# TestMod_SEAx_Base.net
KiCad netlist of a schematic drawn in Altium Designer
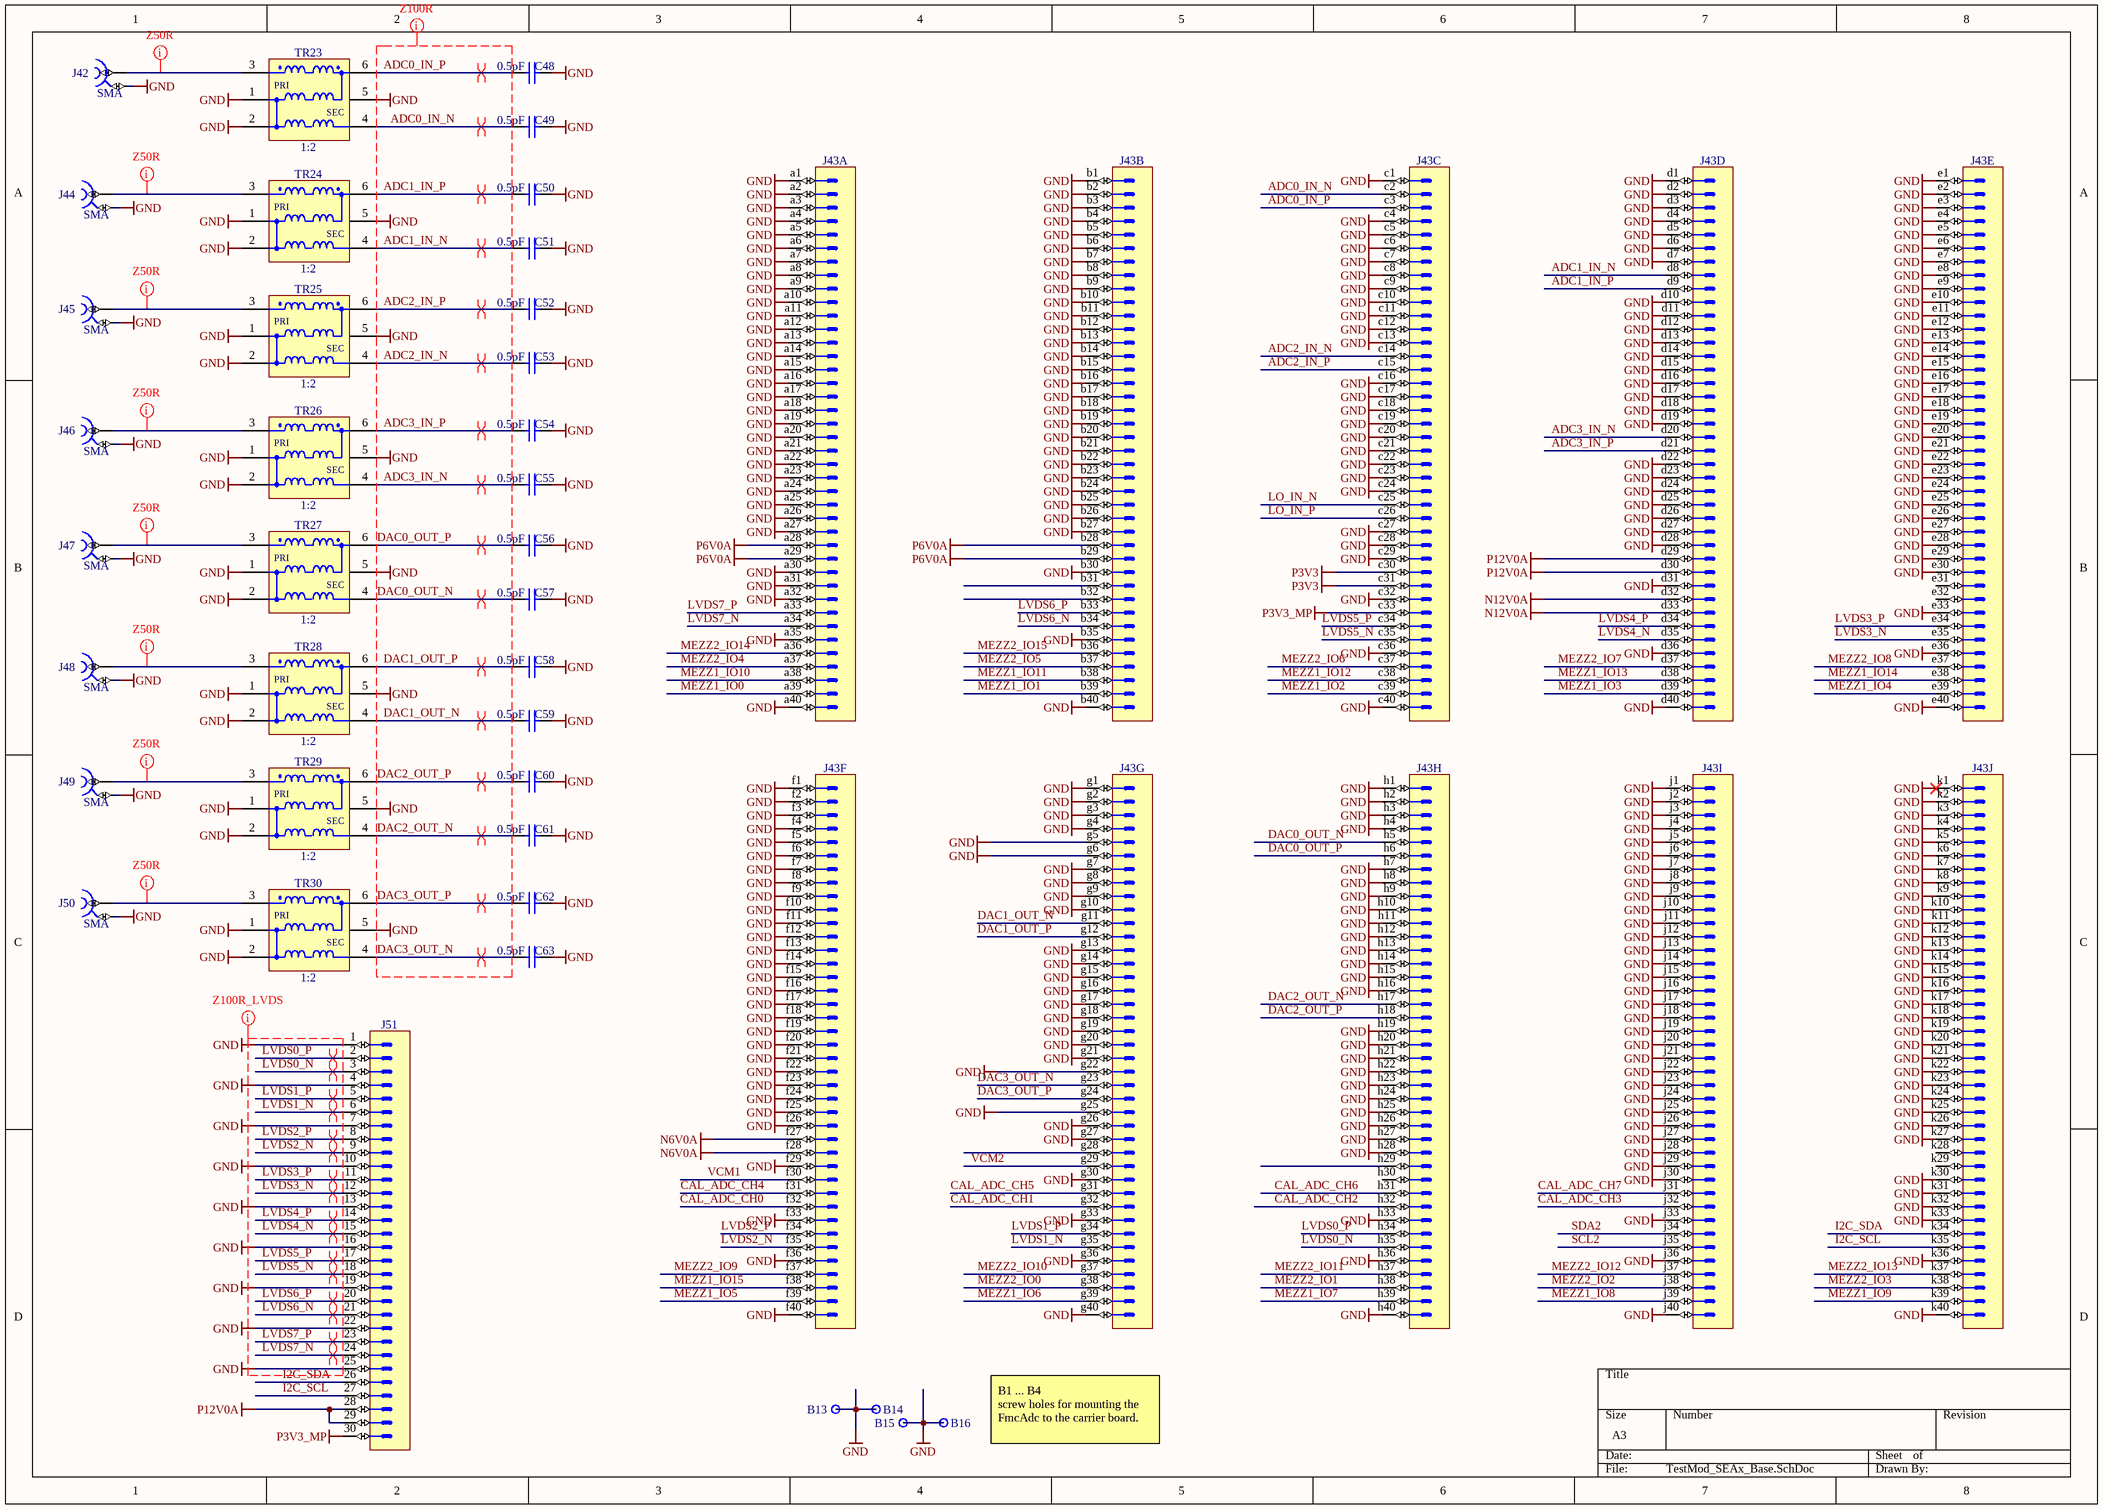
[diagram p0: TestMod_SEAx_Base.SchDoc]

(export (version "E")
  (design (tool "Eeschema 10.0.6"))
  (components
    (comp (ref "B13")
      (value "Plated Hole")
      (footprint "MTG270_500")
      (description "Single Terminal Socket")
      (fields (field (name "PART NUMBER") "PLATED_HOLE2.7_PAD5.0") (field (name "AUTHOR") "CERN DEM JMW"))
      (libsource (lib "Eletro-mechanical") (part "Single Terminal Socket"))
    )
    (comp (ref "B14")
      (value "Plated Hole")
      (footprint "MTG270_500")
      (description "Single Terminal Socket")
      (fields (field (name "PART NUMBER") "PLATED_HOLE2.7_PAD5.0") (field (name "AUTHOR") "CERN DEM JMW"))
      (libsource (lib "Eletro-mechanical") (part "Single Terminal Socket"))
    )
    (comp (ref "B15")
      (value "Plated Hole")
      (footprint "MTG270_500")
      (description "Single Terminal Socket")
      (fields (field (name "PART NUMBER") "PLATED_HOLE2.7_PAD5.0") (field (name "AUTHOR") "CERN DEM JMW"))
      (libsource (lib "Eletro-mechanical") (part "Single Terminal Socket"))
    )
    (comp (ref "B16")
      (value "Plated Hole")
      (footprint "MTG270_500")
      (description "Single Terminal Socket")
      (fields (field (name "PART NUMBER") "PLATED_HOLE2.7_PAD5.0") (field (name "AUTHOR") "CERN DEM JMW"))
      (libsource (lib "Eletro-mechanical") (part "Single Terminal Socket"))
    )
    (comp (ref "C48")
      (value "0.5pF")
      (footprint "CAPC1005X50N")
      (description "Non-polarised capacitor")
      (fields
        (field (name "PART NUMBER") "CC0402_0.5PF_25V_0.05PF_AVX_04023J0R5ABSTR")
        (field (name "VOLTAGE") "25V")
        (field (name "AUTHOR") "CERN DEM JLC")
      )
      (libsource (lib "Capacitors") (part "Capacitor - non polarized"))
    )
    (comp (ref "C49")
      (value "0.5pF")
      (footprint "CAPC1005X50N")
      (description "Non-polarised capacitor")
      (fields
        (field (name "PART NUMBER") "CC0402_0.5PF_25V_0.05PF_AVX_04023J0R5ABSTR")
        (field (name "VOLTAGE") "25V")
        (field (name "AUTHOR") "CERN DEM JLC")
      )
      (libsource (lib "Capacitors") (part "Capacitor - non polarized"))
    )
    (comp (ref "C50")
      (value "0.5pF")
      (footprint "CAPC1005X50N")
      (description "Non-polarised capacitor")
      (fields
        (field (name "PART NUMBER") "CC0402_0.5PF_25V_0.05PF_AVX_04023J0R5ABSTR")
        (field (name "VOLTAGE") "25V")
        (field (name "AUTHOR") "CERN DEM JLC")
      )
      (libsource (lib "Capacitors") (part "Capacitor - non polarized"))
    )
    (comp (ref "C51")
      (value "0.5pF")
      (footprint "CAPC1005X50N")
      (description "Non-polarised capacitor")
      (fields
        (field (name "PART NUMBER") "CC0402_0.5PF_25V_0.05PF_AVX_04023J0R5ABSTR")
        (field (name "VOLTAGE") "25V")
        (field (name "AUTHOR") "CERN DEM JLC")
      )
      (libsource (lib "Capacitors") (part "Capacitor - non polarized"))
    )
    (comp (ref "C52")
      (value "0.5pF")
      (footprint "CAPC1005X50N")
      (description "Non-polarised capacitor")
      (fields
        (field (name "PART NUMBER") "CC0402_0.5PF_25V_0.05PF_AVX_04023J0R5ABSTR")
        (field (name "VOLTAGE") "25V")
        (field (name "AUTHOR") "CERN DEM JLC")
      )
      (libsource (lib "Capacitors") (part "Capacitor - non polarized"))
    )
    (comp (ref "C53")
      (value "0.5pF")
      (footprint "CAPC1005X50N")
      (description "Non-polarised capacitor")
      (fields
        (field (name "PART NUMBER") "CC0402_0.5PF_25V_0.05PF_AVX_04023J0R5ABSTR")
        (field (name "VOLTAGE") "25V")
        (field (name "AUTHOR") "CERN DEM JLC")
      )
      (libsource (lib "Capacitors") (part "Capacitor - non polarized"))
    )
    (comp (ref "C54")
      (value "0.5pF")
      (footprint "CAPC1005X50N")
      (description "Non-polarised capacitor")
      (fields
        (field (name "PART NUMBER") "CC0402_0.5PF_25V_0.05PF_AVX_04023J0R5ABSTR")
        (field (name "VOLTAGE") "25V")
        (field (name "AUTHOR") "CERN DEM JLC")
      )
      (libsource (lib "Capacitors") (part "Capacitor - non polarized"))
    )
    (comp (ref "C55")
      (value "0.5pF")
      (footprint "CAPC1005X50N")
      (description "Non-polarised capacitor")
      (fields
        (field (name "PART NUMBER") "CC0402_0.5PF_25V_0.05PF_AVX_04023J0R5ABSTR")
        (field (name "VOLTAGE") "25V")
        (field (name "AUTHOR") "CERN DEM JLC")
      )
      (libsource (lib "Capacitors") (part "Capacitor - non polarized"))
    )
    (comp (ref "C56")
      (value "0.5pF")
      (footprint "CAPC1005X50N")
      (description "Non-polarised capacitor")
      (fields
        (field (name "PART NUMBER") "CC0402_0.5PF_25V_0.05PF_AVX_04023J0R5ABSTR")
        (field (name "VOLTAGE") "25V")
        (field (name "AUTHOR") "CERN DEM JLC")
      )
      (libsource (lib "Capacitors") (part "Capacitor - non polarized"))
    )
    (comp (ref "C57")
      (value "0.5pF")
      (footprint "CAPC1005X50N")
      (description "Non-polarised capacitor")
      (fields
        (field (name "PART NUMBER") "CC0402_0.5PF_25V_0.05PF_AVX_04023J0R5ABSTR")
        (field (name "VOLTAGE") "25V")
        (field (name "AUTHOR") "CERN DEM JLC")
      )
      (libsource (lib "Capacitors") (part "Capacitor - non polarized"))
    )
    (comp (ref "C58")
      (value "0.5pF")
      (footprint "CAPC1005X50N")
      (description "Non-polarised capacitor")
      (fields
        (field (name "PART NUMBER") "CC0402_0.5PF_25V_0.05PF_AVX_04023J0R5ABSTR")
        (field (name "VOLTAGE") "25V")
        (field (name "AUTHOR") "CERN DEM JLC")
      )
      (libsource (lib "Capacitors") (part "Capacitor - non polarized"))
    )
    (comp (ref "C59")
      (value "0.5pF")
      (footprint "CAPC1005X50N")
      (description "Non-polarised capacitor")
      (fields
        (field (name "PART NUMBER") "CC0402_0.5PF_25V_0.05PF_AVX_04023J0R5ABSTR")
        (field (name "VOLTAGE") "25V")
        (field (name "AUTHOR") "CERN DEM JLC")
      )
      (libsource (lib "Capacitors") (part "Capacitor - non polarized"))
    )
    (comp (ref "C60")
      (value "0.5pF")
      (footprint "CAPC1005X50N")
      (description "Non-polarised capacitor")
      (fields
        (field (name "PART NUMBER") "CC0402_0.5PF_25V_0.05PF_AVX_04023J0R5ABSTR")
        (field (name "VOLTAGE") "25V")
        (field (name "AUTHOR") "CERN DEM JLC")
      )
      (libsource (lib "Capacitors") (part "Capacitor - non polarized"))
    )
    (comp (ref "C61")
      (value "0.5pF")
      (footprint "CAPC1005X50N")
      (description "Non-polarised capacitor")
      (fields
        (field (name "PART NUMBER") "CC0402_0.5PF_25V_0.05PF_AVX_04023J0R5ABSTR")
        (field (name "VOLTAGE") "25V")
        (field (name "AUTHOR") "CERN DEM JLC")
      )
      (libsource (lib "Capacitors") (part "Capacitor - non polarized"))
    )
    (comp (ref "C62")
      (value "0.5pF")
      (footprint "CAPC1005X50N")
      (description "Non-polarised capacitor")
      (fields
        (field (name "PART NUMBER") "CC0402_0.5PF_25V_0.05PF_AVX_04023J0R5ABSTR")
        (field (name "VOLTAGE") "25V")
        (field (name "AUTHOR") "CERN DEM JLC")
      )
      (libsource (lib "Capacitors") (part "Capacitor - non polarized"))
    )
    (comp (ref "C63")
      (value "0.5pF")
      (footprint "CAPC1005X50N")
      (description "Non-polarised capacitor")
      (fields
        (field (name "PART NUMBER") "CC0402_0.5PF_25V_0.05PF_AVX_04023J0R5ABSTR")
        (field (name "VOLTAGE") "25V")
        (field (name "AUTHOR") "CERN DEM JLC")
      )
      (libsource (lib "Capacitors") (part "Capacitor - non polarized"))
    )
    (comp (ref "J42")
      (value "SMA")
      (footprint "TYCO_5-1814832-1")
      (fields
        (field (name "PART NUMBER") "TYCO_5-1814832-1")
        (field (name "MANUFACTURER") "TYCO ELECTRONICS")
        (field (name "MANUFACTURER PART NUMBER") "5-1814832-1")
        (field (name "AUTHOR") "CERN DEM JLC")
      )
      (libsource (lib "Connectors") (part "Coax_1Female_1Shield"))
    )
    (comp (ref "J43")
      (value "VITA 57")
      (footprint "SAMTEC_ASP-134488-01")
      (description "Connector VITA 57, 400 Male contacts in 10 row abcdefghj")
      (fields
        (field (name "PART NUMBER") "SAMTEC_ASP-134488-01")
        (field (name "MANUFACTURER") "SAMTEC")
        (field (name "AUTHOR") "CERN DEM JLC")
      )
      (libsource (lib "Connectors") (part "Connector VITA 57 400 Male (abcdefghjk)"))
    )
    (comp (ref "J44")
      (value "SMA")
      (footprint "TYCO_5-1814832-1")
      (fields
        (field (name "PART NUMBER") "TYCO_5-1814832-1")
        (field (name "MANUFACTURER") "TYCO ELECTRONICS")
        (field (name "MANUFACTURER PART NUMBER") "5-1814832-1")
        (field (name "AUTHOR") "CERN DEM JLC")
      )
      (libsource (lib "Connectors") (part "Coax_1Female_1Shield"))
    )
    (comp (ref "J45")
      (value "SMA")
      (footprint "TYCO_5-1814832-1")
      (fields
        (field (name "PART NUMBER") "TYCO_5-1814832-1")
        (field (name "MANUFACTURER") "TYCO ELECTRONICS")
        (field (name "MANUFACTURER PART NUMBER") "5-1814832-1")
        (field (name "AUTHOR") "CERN DEM JLC")
      )
      (libsource (lib "Connectors") (part "Coax_1Female_1Shield"))
    )
    (comp (ref "J46")
      (value "SMA")
      (footprint "TYCO_5-1814832-1")
      (fields
        (field (name "PART NUMBER") "TYCO_5-1814832-1")
        (field (name "MANUFACTURER") "TYCO ELECTRONICS")
        (field (name "MANUFACTURER PART NUMBER") "5-1814832-1")
        (field (name "AUTHOR") "CERN DEM JLC")
      )
      (libsource (lib "Connectors") (part "Coax_1Female_1Shield"))
    )
    (comp (ref "J47")
      (value "SMA")
      (footprint "TYCO_5-1814832-1")
      (fields
        (field (name "PART NUMBER") "TYCO_5-1814832-1")
        (field (name "MANUFACTURER") "TYCO ELECTRONICS")
        (field (name "MANUFACTURER PART NUMBER") "5-1814832-1")
        (field (name "AUTHOR") "CERN DEM JLC")
      )
      (libsource (lib "Connectors") (part "Coax_1Female_1Shield"))
    )
    (comp (ref "J48")
      (value "SMA")
      (footprint "TYCO_5-1814832-1")
      (fields
        (field (name "PART NUMBER") "TYCO_5-1814832-1")
        (field (name "MANUFACTURER") "TYCO ELECTRONICS")
        (field (name "MANUFACTURER PART NUMBER") "5-1814832-1")
        (field (name "AUTHOR") "CERN DEM JLC")
      )
      (libsource (lib "Connectors") (part "Coax_1Female_1Shield"))
    )
    (comp (ref "J49")
      (value "SMA")
      (footprint "TYCO_5-1814832-1")
      (fields
        (field (name "PART NUMBER") "TYCO_5-1814832-1")
        (field (name "MANUFACTURER") "TYCO ELECTRONICS")
        (field (name "MANUFACTURER PART NUMBER") "5-1814832-1")
        (field (name "AUTHOR") "CERN DEM JLC")
      )
      (libsource (lib "Connectors") (part "Coax_1Female_1Shield"))
    )
    (comp (ref "J50")
      (value "SMA")
      (footprint "TYCO_5-1814832-1")
      (fields
        (field (name "PART NUMBER") "TYCO_5-1814832-1")
        (field (name "MANUFACTURER") "TYCO ELECTRONICS")
        (field (name "MANUFACTURER PART NUMBER") "5-1814832-1")
        (field (name "AUTHOR") "CERN DEM JLC")
      )
      (libsource (lib "Connectors") (part "Coax_1Female_1Shield"))
    )
    (comp (ref "J51")
      (value "~")
      (footprint "3M_N2530-6002RB")
      (description "Connector 30 Male")
      (fields
        (field (name "PART NUMBER") "3M_N2530-6002RB")
        (field (name "MANUFACTURER") "3M")
        (field (name "AUTHOR") "CERN DEM JLC")
      )
      (libsource (lib "Connectors") (part "Connector 30 Male"))
    )
    (comp (ref "TR23")
      (value "1:2")
      (footprint "XFMR_MINI-CIRCUITS_DB1627")
      (description "50 OHMS 10 to 4000 MHz RF Transformer")
      (fields
        (field (name "PART NUMBER") "XFMR_MINI-CIRCUITS_TCM2-43X+")
        (field (name "POWER") "0.4W")
        (field (name "AUTHOR") "CERN DEM BC")
      )
      (libsource (lib "Inductors & Transformers") (part "XFMR_MINI-CIRCUITS_TCM2-43X"))
    )
    (comp (ref "TR24")
      (value "1:2")
      (footprint "XFMR_MINI-CIRCUITS_DB1627")
      (description "50 OHMS 10 to 4000 MHz RF Transformer")
      (fields
        (field (name "PART NUMBER") "XFMR_MINI-CIRCUITS_TCM2-43X+")
        (field (name "POWER") "0.4W")
        (field (name "AUTHOR") "CERN DEM BC")
      )
      (libsource (lib "Inductors & Transformers") (part "XFMR_MINI-CIRCUITS_TCM2-43X"))
    )
    (comp (ref "TR25")
      (value "1:2")
      (footprint "XFMR_MINI-CIRCUITS_DB1627")
      (description "50 OHMS 10 to 4000 MHz RF Transformer")
      (fields
        (field (name "PART NUMBER") "XFMR_MINI-CIRCUITS_TCM2-43X+")
        (field (name "POWER") "0.4W")
        (field (name "AUTHOR") "CERN DEM BC")
      )
      (libsource (lib "Inductors & Transformers") (part "XFMR_MINI-CIRCUITS_TCM2-43X"))
    )
    (comp (ref "TR26")
      (value "1:2")
      (footprint "XFMR_MINI-CIRCUITS_DB1627")
      (description "50 OHMS 10 to 4000 MHz RF Transformer")
      (fields
        (field (name "PART NUMBER") "XFMR_MINI-CIRCUITS_TCM2-43X+")
        (field (name "POWER") "0.4W")
        (field (name "AUTHOR") "CERN DEM BC")
      )
      (libsource (lib "Inductors & Transformers") (part "XFMR_MINI-CIRCUITS_TCM2-43X"))
    )
    (comp (ref "TR27")
      (value "1:2")
      (footprint "XFMR_MINI-CIRCUITS_DB1627")
      (description "50 OHMS 10 to 4000 MHz RF Transformer")
      (fields
        (field (name "PART NUMBER") "XFMR_MINI-CIRCUITS_TCM2-43X+")
        (field (name "POWER") "0.4W")
        (field (name "AUTHOR") "CERN DEM BC")
      )
      (libsource (lib "Inductors & Transformers") (part "XFMR_MINI-CIRCUITS_TCM2-43X"))
    )
    (comp (ref "TR28")
      (value "1:2")
      (footprint "XFMR_MINI-CIRCUITS_DB1627")
      (description "50 OHMS 10 to 4000 MHz RF Transformer")
      (fields
        (field (name "PART NUMBER") "XFMR_MINI-CIRCUITS_TCM2-43X+")
        (field (name "POWER") "0.4W")
        (field (name "AUTHOR") "CERN DEM BC")
      )
      (libsource (lib "Inductors & Transformers") (part "XFMR_MINI-CIRCUITS_TCM2-43X"))
    )
    (comp (ref "TR29")
      (value "1:2")
      (footprint "XFMR_MINI-CIRCUITS_DB1627")
      (description "50 OHMS 10 to 4000 MHz RF Transformer")
      (fields
        (field (name "PART NUMBER") "XFMR_MINI-CIRCUITS_TCM2-43X+")
        (field (name "POWER") "0.4W")
        (field (name "AUTHOR") "CERN DEM BC")
      )
      (libsource (lib "Inductors & Transformers") (part "XFMR_MINI-CIRCUITS_TCM2-43X"))
    )
    (comp (ref "TR30")
      (value "1:2")
      (footprint "XFMR_MINI-CIRCUITS_DB1627")
      (description "50 OHMS 10 to 4000 MHz RF Transformer")
      (fields
        (field (name "PART NUMBER") "XFMR_MINI-CIRCUITS_TCM2-43X+")
        (field (name "POWER") "0.4W")
        (field (name "AUTHOR") "CERN DEM BC")
      )
      (libsource (lib "Inductors & Transformers") (part "XFMR_MINI-CIRCUITS_TCM2-43X"))
    )
  )
  (nets
    (net (code "1") (name "/ADC0_IN_N") (class "Default")
      (node (ref "C49") (pin "1") (pinfunction "1_1") (pintype "passive"))
      (node (ref "J43") (pin "c2") (pinfunction "c2_c2") (pintype "bidirectional"))
      (node (ref "TR23") (pin "4") (pinfunction "S1_4") (pintype "passive"))
    )
    (net (code "2") (name "/ADC0_IN_P") (class "Default")
      (node (ref "C48") (pin "1") (pinfunction "1_1") (pintype "passive"))
      (node (ref "J43") (pin "c3") (pinfunction "c3_c3") (pintype "bidirectional"))
      (node (ref "TR23") (pin "6") (pinfunction "S1_6") (pintype "passive"))
    )
    (net (code "3") (name "/ADC1_IN_N") (class "Default")
      (node (ref "C51") (pin "1") (pinfunction "1_1") (pintype "passive"))
      (node (ref "J43") (pin "d8") (pinfunction "d8_d8") (pintype "bidirectional"))
      (node (ref "TR24") (pin "4") (pinfunction "S1_4") (pintype "passive"))
    )
    (net (code "4") (name "/ADC1_IN_P") (class "Default")
      (node (ref "C50") (pin "1") (pinfunction "1_1") (pintype "passive"))
      (node (ref "J43") (pin "d9") (pinfunction "d9_d9") (pintype "bidirectional"))
      (node (ref "TR24") (pin "6") (pinfunction "S1_6") (pintype "passive"))
    )
    (net (code "5") (name "/ADC2_IN_N") (class "Default")
      (node (ref "C53") (pin "1") (pinfunction "1_1") (pintype "passive"))
      (node (ref "J43") (pin "c14") (pinfunction "c14_c14") (pintype "bidirectional"))
      (node (ref "TR25") (pin "4") (pinfunction "S1_4") (pintype "passive"))
    )
    (net (code "6") (name "/ADC2_IN_P") (class "Default")
      (node (ref "C52") (pin "1") (pinfunction "1_1") (pintype "passive"))
      (node (ref "J43") (pin "c15") (pinfunction "c15_c15") (pintype "bidirectional"))
      (node (ref "TR25") (pin "6") (pinfunction "S1_6") (pintype "passive"))
    )
    (net (code "7") (name "/ADC3_IN_N") (class "Default")
      (node (ref "C55") (pin "1") (pinfunction "1_1") (pintype "passive"))
      (node (ref "J43") (pin "d20") (pinfunction "d20_d20") (pintype "bidirectional"))
      (node (ref "TR26") (pin "4") (pinfunction "S1_4") (pintype "passive"))
    )
    (net (code "8") (name "/ADC3_IN_P") (class "Default")
      (node (ref "C54") (pin "1") (pinfunction "1_1") (pintype "passive"))
      (node (ref "J43") (pin "d21") (pinfunction "d21_d21") (pintype "bidirectional"))
      (node (ref "TR26") (pin "6") (pinfunction "S1_6") (pintype "passive"))
    )
    (net (code "10") (name "/CAL_ADC_CH0") (class "Default")
      (node (ref "J43") (pin "f32") (pinfunction "f32_f32") (pintype "bidirectional"))
    )
    (net (code "11") (name "/CAL_ADC_CH1") (class "Default")
      (node (ref "J43") (pin "g32") (pinfunction "g32_g32") (pintype "bidirectional"))
    )
    (net (code "12") (name "/CAL_ADC_CH2") (class "Default")
      (node (ref "J43") (pin "h32") (pinfunction "h32_h32") (pintype "bidirectional"))
    )
    (net (code "13") (name "/CAL_ADC_CH3") (class "Default")
      (node (ref "J43") (pin "j32") (pinfunction "j32_j32") (pintype "bidirectional"))
    )
    (net (code "14") (name "/CAL_ADC_CH4") (class "Default")
      (node (ref "J43") (pin "f31") (pinfunction "f31_f31") (pintype "bidirectional"))
    )
    (net (code "15") (name "/CAL_ADC_CH5") (class "Default")
      (node (ref "J43") (pin "g31") (pinfunction "g31_g31") (pintype "bidirectional"))
    )
    (net (code "16") (name "/CAL_ADC_CH6") (class "Default")
      (node (ref "J43") (pin "h31") (pinfunction "h31_h31") (pintype "bidirectional"))
    )
    (net (code "17") (name "/CAL_ADC_CH7") (class "Default")
      (node (ref "J43") (pin "j31") (pinfunction "j31_j31") (pintype "bidirectional"))
    )
    (net (code "18") (name "/DAC0_OUT_N") (class "Default")
      (node (ref "C57") (pin "1") (pinfunction "1_1") (pintype "passive"))
      (node (ref "J43") (pin "h5") (pinfunction "h5_h5") (pintype "bidirectional"))
      (node (ref "TR27") (pin "4") (pinfunction "S1_4") (pintype "passive"))
    )
    (net (code "19") (name "/DAC0_OUT_P") (class "Default")
      (node (ref "C56") (pin "1") (pinfunction "1_1") (pintype "passive"))
      (node (ref "J43") (pin "h6") (pinfunction "h6_h6") (pintype "bidirectional"))
      (node (ref "TR27") (pin "6") (pinfunction "S1_6") (pintype "passive"))
    )
    (net (code "20") (name "/DAC1_OUT_N") (class "Default")
      (node (ref "C59") (pin "1") (pinfunction "1_1") (pintype "passive"))
      (node (ref "J43") (pin "g11") (pinfunction "g11_g11") (pintype "bidirectional"))
      (node (ref "TR28") (pin "4") (pinfunction "S1_4") (pintype "passive"))
    )
    (net (code "21") (name "/DAC1_OUT_P") (class "Default")
      (node (ref "C58") (pin "1") (pinfunction "1_1") (pintype "passive"))
      (node (ref "J43") (pin "g12") (pinfunction "g12_g12") (pintype "bidirectional"))
      (node (ref "TR28") (pin "6") (pinfunction "S1_6") (pintype "passive"))
    )
    (net (code "22") (name "/DAC2_OUT_N") (class "Default")
      (node (ref "C61") (pin "1") (pinfunction "1_1") (pintype "passive"))
      (node (ref "J43") (pin "h17") (pinfunction "h17_h17") (pintype "bidirectional"))
      (node (ref "TR29") (pin "4") (pinfunction "S1_4") (pintype "passive"))
    )
    (net (code "23") (name "/DAC2_OUT_P") (class "Default")
      (node (ref "C60") (pin "1") (pinfunction "1_1") (pintype "passive"))
      (node (ref "J43") (pin "h18") (pinfunction "h18_h18") (pintype "bidirectional"))
      (node (ref "TR29") (pin "6") (pinfunction "S1_6") (pintype "passive"))
    )
    (net (code "24") (name "/DAC3_OUT_N") (class "Default")
      (node (ref "C63") (pin "1") (pinfunction "1_1") (pintype "passive"))
      (node (ref "J43") (pin "g23") (pinfunction "g23_g23") (pintype "bidirectional"))
      (node (ref "TR30") (pin "4") (pinfunction "S1_4") (pintype "passive"))
    )
    (net (code "25") (name "/DAC3_OUT_P") (class "Default")
      (node (ref "C62") (pin "1") (pinfunction "1_1") (pintype "passive"))
      (node (ref "J43") (pin "g24") (pinfunction "g24_g24") (pintype "bidirectional"))
      (node (ref "TR30") (pin "6") (pinfunction "S1_6") (pintype "passive"))
    )
    (net (code "26") (name "/I2C_SCL") (class "Default")
      (node (ref "J43") (pin "k35") (pinfunction "k35_k35") (pintype "bidirectional"))
      (node (ref "J51") (pin "27") (pinfunction "27_27") (pintype "bidirectional"))
    )
    (net (code "27") (name "/I2C_SDA") (class "Default")
      (node (ref "J43") (pin "k34") (pinfunction "k34_k34") (pintype "bidirectional"))
      (node (ref "J51") (pin "26") (pinfunction "26_26") (pintype "bidirectional"))
    )
    (net (code "28") (name "/LO_IN_N") (class "Default")
      (node (ref "J43") (pin "c25") (pinfunction "c25_c25") (pintype "bidirectional"))
    )
    (net (code "29") (name "/LO_IN_P") (class "Default")
      (node (ref "J43") (pin "c26") (pinfunction "c26_c26") (pintype "bidirectional"))
    )
    (net (code "30") (name "/LVDS0_N") (class "Default")
      (node (ref "J43") (pin "h35") (pinfunction "h35_h35") (pintype "bidirectional"))
      (node (ref "J51") (pin "3") (pinfunction "3_3") (pintype "bidirectional"))
    )
    (net (code "31") (name "/LVDS0_P") (class "Default")
      (node (ref "J43") (pin "h34") (pinfunction "h34_h34") (pintype "bidirectional"))
      (node (ref "J51") (pin "2") (pinfunction "2_2") (pintype "bidirectional"))
    )
    (net (code "32") (name "/LVDS1_N") (class "Default")
      (node (ref "J43") (pin "g35") (pinfunction "g35_g35") (pintype "bidirectional"))
      (node (ref "J51") (pin "6") (pinfunction "6_6") (pintype "bidirectional"))
    )
    (net (code "33") (name "/LVDS1_P") (class "Default")
      (node (ref "J43") (pin "g34") (pinfunction "g34_g34") (pintype "bidirectional"))
      (node (ref "J51") (pin "5") (pinfunction "5_5") (pintype "bidirectional"))
    )
    (net (code "34") (name "/LVDS2_N") (class "Default")
      (node (ref "J43") (pin "f35") (pinfunction "f35_f35") (pintype "bidirectional"))
      (node (ref "J51") (pin "9") (pinfunction "9_9") (pintype "bidirectional"))
    )
    (net (code "35") (name "/LVDS2_P") (class "Default")
      (node (ref "J43") (pin "f34") (pinfunction "f34_f34") (pintype "bidirectional"))
      (node (ref "J51") (pin "8") (pinfunction "8_8") (pintype "bidirectional"))
    )
    (net (code "36") (name "/LVDS3_N") (class "Default")
      (node (ref "J43") (pin "e35") (pinfunction "e35_e35") (pintype "bidirectional"))
      (node (ref "J51") (pin "12") (pinfunction "12_12") (pintype "bidirectional"))
    )
    (net (code "37") (name "/LVDS3_P") (class "Default")
      (node (ref "J43") (pin "e34") (pinfunction "e34_e34") (pintype "bidirectional"))
      (node (ref "J51") (pin "11") (pinfunction "11_11") (pintype "bidirectional"))
    )
    (net (code "38") (name "/LVDS4_N") (class "Default")
      (node (ref "J43") (pin "d35") (pinfunction "d35_d35") (pintype "bidirectional"))
      (node (ref "J51") (pin "15") (pinfunction "15_15") (pintype "bidirectional"))
    )
    (net (code "39") (name "/LVDS4_P") (class "Default")
      (node (ref "J43") (pin "d34") (pinfunction "d34_d34") (pintype "bidirectional"))
      (node (ref "J51") (pin "14") (pinfunction "14_14") (pintype "bidirectional"))
    )
    (net (code "40") (name "/LVDS5_N") (class "Default")
      (node (ref "J43") (pin "c35") (pinfunction "c35_c35") (pintype "bidirectional"))
      (node (ref "J51") (pin "18") (pinfunction "18_18") (pintype "bidirectional"))
    )
    (net (code "41") (name "/LVDS5_P") (class "Default")
      (node (ref "J43") (pin "c34") (pinfunction "c34_c34") (pintype "bidirectional"))
      (node (ref "J51") (pin "17") (pinfunction "17_17") (pintype "bidirectional"))
    )
    (net (code "42") (name "/LVDS6_N") (class "Default")
      (node (ref "J43") (pin "b34") (pinfunction "b34_b34") (pintype "bidirectional"))
      (node (ref "J51") (pin "21") (pinfunction "21_21") (pintype "bidirectional"))
    )
    (net (code "43") (name "/LVDS6_P") (class "Default")
      (node (ref "J43") (pin "b33") (pinfunction "b33_b33") (pintype "bidirectional"))
      (node (ref "J51") (pin "20") (pinfunction "20_20") (pintype "bidirectional"))
    )
    (net (code "44") (name "/LVDS7_N") (class "Default")
      (node (ref "J43") (pin "a34") (pinfunction "a34_a34") (pintype "bidirectional"))
      (node (ref "J51") (pin "24") (pinfunction "24_24") (pintype "bidirectional"))
    )
    (net (code "45") (name "/LVDS7_P") (class "Default")
      (node (ref "J43") (pin "a33") (pinfunction "a33_a33") (pintype "bidirectional"))
      (node (ref "J51") (pin "23") (pinfunction "23_23") (pintype "bidirectional"))
    )
    (net (code "46") (name "/MEZZ1_IO0") (class "Default")
      (node (ref "J43") (pin "a39") (pinfunction "a39_a39") (pintype "bidirectional"))
    )
    (net (code "47") (name "/MEZZ1_IO1") (class "Default")
      (node (ref "J43") (pin "b39") (pinfunction "b39_b39") (pintype "bidirectional"))
    )
    (net (code "48") (name "/MEZZ1_IO2") (class "Default")
      (node (ref "J43") (pin "c39") (pinfunction "c39_c39") (pintype "bidirectional"))
    )
    (net (code "49") (name "/MEZZ1_IO3") (class "Default")
      (node (ref "J43") (pin "d39") (pinfunction "d39_d39") (pintype "bidirectional"))
    )
    (net (code "50") (name "/MEZZ1_IO4") (class "Default")
      (node (ref "J43") (pin "e39") (pinfunction "e39_e39") (pintype "bidirectional"))
    )
    (net (code "51") (name "/MEZZ1_IO5") (class "Default")
      (node (ref "J43") (pin "f39") (pinfunction "f39_f39") (pintype "bidirectional"))
    )
    (net (code "52") (name "/MEZZ1_IO6") (class "Default")
      (node (ref "J43") (pin "g39") (pinfunction "g39_g39") (pintype "bidirectional"))
    )
    (net (code "53") (name "/MEZZ1_IO7") (class "Default")
      (node (ref "J43") (pin "h39") (pinfunction "h39_h39") (pintype "bidirectional"))
    )
    (net (code "54") (name "/MEZZ1_IO8") (class "Default")
      (node (ref "J43") (pin "j39") (pinfunction "j39_j39") (pintype "bidirectional"))
    )
    (net (code "55") (name "/MEZZ1_IO9") (class "Default")
      (node (ref "J43") (pin "k39") (pinfunction "k39_k39") (pintype "bidirectional"))
    )
    (net (code "56") (name "/MEZZ1_IO10") (class "Default")
      (node (ref "J43") (pin "a38") (pinfunction "a38_a38") (pintype "bidirectional"))
    )
    (net (code "57") (name "/MEZZ1_IO11") (class "Default")
      (node (ref "J43") (pin "b38") (pinfunction "b38_b38") (pintype "bidirectional"))
    )
    (net (code "58") (name "/MEZZ1_IO12") (class "Default")
      (node (ref "J43") (pin "c38") (pinfunction "c38_c38") (pintype "bidirectional"))
    )
    (net (code "59") (name "/MEZZ1_IO13") (class "Default")
      (node (ref "J43") (pin "d38") (pinfunction "d38_d38") (pintype "bidirectional"))
    )
    (net (code "60") (name "/MEZZ1_IO14") (class "Default")
      (node (ref "J43") (pin "e38") (pinfunction "e38_e38") (pintype "bidirectional"))
    )
    (net (code "61") (name "/MEZZ1_IO15") (class "Default")
      (node (ref "J43") (pin "f38") (pinfunction "f38_f38") (pintype "bidirectional"))
    )
    (net (code "62") (name "/MEZZ2_IO0") (class "Default")
      (node (ref "J43") (pin "g38") (pinfunction "g38_g38") (pintype "bidirectional"))
    )
    (net (code "63") (name "/MEZZ2_IO1") (class "Default")
      (node (ref "J43") (pin "h38") (pinfunction "h38_h38") (pintype "bidirectional"))
    )
    (net (code "64") (name "/MEZZ2_IO2") (class "Default")
      (node (ref "J43") (pin "j38") (pinfunction "j38_j38") (pintype "bidirectional"))
    )
    (net (code "65") (name "/MEZZ2_IO3") (class "Default")
      (node (ref "J43") (pin "k38") (pinfunction "k38_k38") (pintype "bidirectional"))
    )
    (net (code "66") (name "/MEZZ2_IO4") (class "Default")
      (node (ref "J43") (pin "a37") (pinfunction "a37_a37") (pintype "bidirectional"))
    )
    (net (code "67") (name "/MEZZ2_IO5") (class "Default")
      (node (ref "J43") (pin "b37") (pinfunction "b37_b37") (pintype "bidirectional"))
    )
    (net (code "68") (name "/MEZZ2_IO6") (class "Default")
      (node (ref "J43") (pin "c37") (pinfunction "c37_c37") (pintype "bidirectional"))
    )
    (net (code "69") (name "/MEZZ2_IO7") (class "Default")
      (node (ref "J43") (pin "d37") (pinfunction "d37_d37") (pintype "bidirectional"))
    )
    (net (code "70") (name "/MEZZ2_IO8") (class "Default")
      (node (ref "J43") (pin "e37") (pinfunction "e37_e37") (pintype "bidirectional"))
    )
    (net (code "71") (name "/MEZZ2_IO9") (class "Default")
      (node (ref "J43") (pin "f37") (pinfunction "f37_f37") (pintype "bidirectional"))
    )
    (net (code "72") (name "/MEZZ2_IO10") (class "Default")
      (node (ref "J43") (pin "g37") (pinfunction "g37_g37") (pintype "bidirectional"))
    )
    (net (code "73") (name "/MEZZ2_IO11") (class "Default")
      (node (ref "J43") (pin "h37") (pinfunction "h37_h37") (pintype "bidirectional"))
    )
    (net (code "74") (name "/MEZZ2_IO12") (class "Default")
      (node (ref "J43") (pin "j37") (pinfunction "j37_j37") (pintype "bidirectional"))
    )
    (net (code "75") (name "/MEZZ2_IO13") (class "Default")
      (node (ref "J43") (pin "k37") (pinfunction "k37_k37") (pintype "bidirectional"))
    )
    (net (code "76") (name "/MEZZ2_IO14") (class "Default")
      (node (ref "J43") (pin "a36") (pinfunction "a36_a36") (pintype "bidirectional"))
    )
    (net (code "77") (name "/MEZZ2_IO15") (class "Default")
      (node (ref "J43") (pin "b36") (pinfunction "b36_b36") (pintype "bidirectional"))
    )
    (net (code "78") (name "/SCL2") (class "Default")
      (node (ref "J43") (pin "j35") (pinfunction "j35_j35") (pintype "bidirectional"))
    )
    (net (code "79") (name "/SDA2") (class "Default")
      (node (ref "J43") (pin "j34") (pinfunction "j34_j34") (pintype "bidirectional"))
    )
    (net (code "80") (name "/VCM1") (class "Default")
      (node (ref "J43") (pin "f30") (pinfunction "f30_f30") (pintype "bidirectional"))
    )
    (net (code "81") (name "/VCM2") (class "Default")
      (node (ref "J43") (pin "g29") (pinfunction "g29_g29") (pintype "bidirectional"))
    )
    (net (code "82") (name "GND") (class "Default")
      (node (ref "B13") (pin "1") (pinfunction "1_1") (pintype "bidirectional"))
      (node (ref "B14") (pin "1") (pinfunction "1_1") (pintype "bidirectional"))
      (node (ref "B15") (pin "1") (pinfunction "1_1") (pintype "bidirectional"))
      (node (ref "B16") (pin "1") (pinfunction "1_1") (pintype "bidirectional"))
      (node (ref "C48") (pin "2") (pinfunction "2_2") (pintype "passive"))
      (node (ref "C49") (pin "2") (pinfunction "2_2") (pintype "passive"))
      (node (ref "C50") (pin "2") (pinfunction "2_2") (pintype "passive"))
      (node (ref "C51") (pin "2") (pinfunction "2_2") (pintype "passive"))
      (node (ref "C52") (pin "2") (pinfunction "2_2") (pintype "passive"))
      (node (ref "C53") (pin "2") (pinfunction "2_2") (pintype "passive"))
      (node (ref "C54") (pin "2") (pinfunction "2_2") (pintype "passive"))
      (node (ref "C55") (pin "2") (pinfunction "2_2") (pintype "passive"))
      (node (ref "C56") (pin "2") (pinfunction "2_2") (pintype "passive"))
      (node (ref "C57") (pin "2") (pinfunction "2_2") (pintype "passive"))
      (node (ref "C58") (pin "2") (pinfunction "2_2") (pintype "passive"))
      (node (ref "C59") (pin "2") (pinfunction "2_2") (pintype "passive"))
      (node (ref "C60") (pin "2") (pinfunction "2_2") (pintype "passive"))
      (node (ref "C61") (pin "2") (pinfunction "2_2") (pintype "passive"))
      (node (ref "C62") (pin "2") (pinfunction "2_2") (pintype "passive"))
      (node (ref "C63") (pin "2") (pinfunction "2_2") (pintype "passive"))
      (node (ref "J42") (pin "2") (pinfunction "2_2") (pintype "bidirectional"))
      (node (ref "J43") (pin "a1") (pinfunction "a1_a1") (pintype "bidirectional"))
      (node (ref "J43") (pin "a10") (pinfunction "a10_a10") (pintype "bidirectional"))
      (node (ref "J43") (pin "a11") (pinfunction "a11_a11") (pintype "bidirectional"))
      (node (ref "J43") (pin "a12") (pinfunction "a12_a12") (pintype "bidirectional"))
      (node (ref "J43") (pin "a13") (pinfunction "a13_a13") (pintype "bidirectional"))
      (node (ref "J43") (pin "a14") (pinfunction "a14_a14") (pintype "bidirectional"))
      (node (ref "J43") (pin "a15") (pinfunction "a15_a15") (pintype "bidirectional"))
      (node (ref "J43") (pin "a16") (pinfunction "a16_a16") (pintype "bidirectional"))
      (node (ref "J43") (pin "a17") (pinfunction "a17_a17") (pintype "bidirectional"))
      (node (ref "J43") (pin "a18") (pinfunction "a18_a18") (pintype "bidirectional"))
      (node (ref "J43") (pin "a19") (pinfunction "a19_a19") (pintype "bidirectional"))
      (node (ref "J43") (pin "a2") (pinfunction "a2_a2") (pintype "bidirectional"))
      (node (ref "J43") (pin "a20") (pinfunction "a20_a20") (pintype "bidirectional"))
      (node (ref "J43") (pin "a21") (pinfunction "a21_a21") (pintype "bidirectional"))
      (node (ref "J43") (pin "a22") (pinfunction "a22_a22") (pintype "bidirectional"))
      (node (ref "J43") (pin "a23") (pinfunction "a23_a23") (pintype "bidirectional"))
      (node (ref "J43") (pin "a24") (pinfunction "a24_a24") (pintype "bidirectional"))
      (node (ref "J43") (pin "a25") (pinfunction "a25_a25") (pintype "bidirectional"))
      (node (ref "J43") (pin "a26") (pinfunction "a26_a26") (pintype "bidirectional"))
      (node (ref "J43") (pin "a27") (pinfunction "a27_a27") (pintype "bidirectional"))
      (node (ref "J43") (pin "a3") (pinfunction "a3_a3") (pintype "bidirectional"))
      (node (ref "J43") (pin "a30") (pinfunction "a30_a30") (pintype "bidirectional"))
      (node (ref "J43") (pin "a31") (pinfunction "a31_a31") (pintype "bidirectional"))
      (node (ref "J43") (pin "a32") (pinfunction "a32_a32") (pintype "bidirectional"))
      (node (ref "J43") (pin "a35") (pinfunction "a35_a35") (pintype "bidirectional"))
      (node (ref "J43") (pin "a4") (pinfunction "a4_a4") (pintype "bidirectional"))
      (node (ref "J43") (pin "a40") (pinfunction "a40_a40") (pintype "bidirectional"))
      (node (ref "J43") (pin "a5") (pinfunction "a5_a5") (pintype "bidirectional"))
      (node (ref "J43") (pin "a6") (pinfunction "a6_a6") (pintype "bidirectional"))
      (node (ref "J43") (pin "a7") (pinfunction "a7_a7") (pintype "bidirectional"))
      (node (ref "J43") (pin "a8") (pinfunction "a8_a8") (pintype "bidirectional"))
      (node (ref "J43") (pin "a9") (pinfunction "a9_a9") (pintype "bidirectional"))
      (node (ref "J43") (pin "b1") (pinfunction "b1_b1") (pintype "bidirectional"))
      (node (ref "J43") (pin "b10") (pinfunction "b10_b10") (pintype "bidirectional"))
      (node (ref "J43") (pin "b11") (pinfunction "b11_b11") (pintype "bidirectional"))
      (node (ref "J43") (pin "b12") (pinfunction "b12_b12") (pintype "bidirectional"))
      (node (ref "J43") (pin "b13") (pinfunction "b13_b13") (pintype "bidirectional"))
      (node (ref "J43") (pin "b14") (pinfunction "b14_b14") (pintype "bidirectional"))
      (node (ref "J43") (pin "b15") (pinfunction "b15_b15") (pintype "bidirectional"))
      (node (ref "J43") (pin "b16") (pinfunction "b16_b16") (pintype "bidirectional"))
      (node (ref "J43") (pin "b17") (pinfunction "b17_b17") (pintype "bidirectional"))
      (node (ref "J43") (pin "b18") (pinfunction "b18_b18") (pintype "bidirectional"))
      (node (ref "J43") (pin "b19") (pinfunction "b19_b19") (pintype "bidirectional"))
      (node (ref "J43") (pin "b2") (pinfunction "b2_b2") (pintype "bidirectional"))
      (node (ref "J43") (pin "b20") (pinfunction "b20_b20") (pintype "bidirectional"))
      (node (ref "J43") (pin "b21") (pinfunction "b21_b21") (pintype "bidirectional"))
      (node (ref "J43") (pin "b22") (pinfunction "b22_b22") (pintype "bidirectional"))
      (node (ref "J43") (pin "b23") (pinfunction "b23_b23") (pintype "bidirectional"))
      (node (ref "J43") (pin "b24") (pinfunction "b24_b24") (pintype "bidirectional"))
      (node (ref "J43") (pin "b25") (pinfunction "b25_b25") (pintype "bidirectional"))
      (node (ref "J43") (pin "b26") (pinfunction "b26_b26") (pintype "bidirectional"))
      (node (ref "J43") (pin "b27") (pinfunction "b27_b27") (pintype "bidirectional"))
      (node (ref "J43") (pin "b3") (pinfunction "b3_b3") (pintype "bidirectional"))
      (node (ref "J43") (pin "b30") (pinfunction "b30_b30") (pintype "bidirectional"))
      (node (ref "J43") (pin "b35") (pinfunction "b35_b35") (pintype "bidirectional"))
      (node (ref "J43") (pin "b4") (pinfunction "b4_b4") (pintype "bidirectional"))
      (node (ref "J43") (pin "b40") (pinfunction "b40_b40") (pintype "bidirectional"))
      (node (ref "J43") (pin "b5") (pinfunction "b5_b5") (pintype "bidirectional"))
      (node (ref "J43") (pin "b6") (pinfunction "b6_b6") (pintype "bidirectional"))
      (node (ref "J43") (pin "b7") (pinfunction "b7_b7") (pintype "bidirectional"))
      (node (ref "J43") (pin "b8") (pinfunction "b8_b8") (pintype "bidirectional"))
      (node (ref "J43") (pin "b9") (pinfunction "b9_b9") (pintype "bidirectional"))
      (node (ref "J43") (pin "c1") (pinfunction "c1_c1") (pintype "bidirectional"))
      (node (ref "J43") (pin "c10") (pinfunction "c10_c10") (pintype "bidirectional"))
      (node (ref "J43") (pin "c11") (pinfunction "c11_c11") (pintype "bidirectional"))
      (node (ref "J43") (pin "c12") (pinfunction "c12_c12") (pintype "bidirectional"))
      (node (ref "J43") (pin "c13") (pinfunction "c13_c13") (pintype "bidirectional"))
      (node (ref "J43") (pin "c16") (pinfunction "c16_c16") (pintype "bidirectional"))
      (node (ref "J43") (pin "c17") (pinfunction "c17_c17") (pintype "bidirectional"))
      (node (ref "J43") (pin "c18") (pinfunction "c18_c18") (pintype "bidirectional"))
      (node (ref "J43") (pin "c19") (pinfunction "c19_c19") (pintype "bidirectional"))
      (node (ref "J43") (pin "c20") (pinfunction "c20_c20") (pintype "bidirectional"))
      (node (ref "J43") (pin "c21") (pinfunction "c21_c21") (pintype "bidirectional"))
      (node (ref "J43") (pin "c22") (pinfunction "c22_c22") (pintype "bidirectional"))
      (node (ref "J43") (pin "c23") (pinfunction "c23_c23") (pintype "bidirectional"))
      (node (ref "J43") (pin "c24") (pinfunction "c24_c24") (pintype "bidirectional"))
      (node (ref "J43") (pin "c27") (pinfunction "c27_c27") (pintype "bidirectional"))
      (node (ref "J43") (pin "c28") (pinfunction "c28_c28") (pintype "bidirectional"))
      (node (ref "J43") (pin "c29") (pinfunction "c29_c29") (pintype "bidirectional"))
      (node (ref "J43") (pin "c32") (pinfunction "c32_c32") (pintype "bidirectional"))
      (node (ref "J43") (pin "c36") (pinfunction "c36_c36") (pintype "bidirectional"))
      (node (ref "J43") (pin "c4") (pinfunction "c4_c4") (pintype "bidirectional"))
      (node (ref "J43") (pin "c40") (pinfunction "c40_c40") (pintype "bidirectional"))
      (node (ref "J43") (pin "c5") (pinfunction "c5_c5") (pintype "bidirectional"))
      (node (ref "J43") (pin "c6") (pinfunction "c6_c6") (pintype "bidirectional"))
      (node (ref "J43") (pin "c7") (pinfunction "c7_c7") (pintype "bidirectional"))
      (node (ref "J43") (pin "c8") (pinfunction "c8_c8") (pintype "bidirectional"))
      (node (ref "J43") (pin "c9") (pinfunction "c9_c9") (pintype "bidirectional"))
      (node (ref "J43") (pin "d1") (pinfunction "d1_d1") (pintype "bidirectional"))
      (node (ref "J43") (pin "d10") (pinfunction "d10_d10") (pintype "bidirectional"))
      (node (ref "J43") (pin "d11") (pinfunction "d11_d11") (pintype "bidirectional"))
      (node (ref "J43") (pin "d12") (pinfunction "d12_d12") (pintype "bidirectional"))
      (node (ref "J43") (pin "d13") (pinfunction "d13_d13") (pintype "bidirectional"))
      (node (ref "J43") (pin "d14") (pinfunction "d14_d14") (pintype "bidirectional"))
      (node (ref "J43") (pin "d15") (pinfunction "d15_d15") (pintype "bidirectional"))
      (node (ref "J43") (pin "d16") (pinfunction "d16_d16") (pintype "bidirectional"))
      (node (ref "J43") (pin "d17") (pinfunction "d17_d17") (pintype "bidirectional"))
      (node (ref "J43") (pin "d18") (pinfunction "d18_d18") (pintype "bidirectional"))
      (node (ref "J43") (pin "d19") (pinfunction "d19_d19") (pintype "bidirectional"))
      (node (ref "J43") (pin "d2") (pinfunction "d2_d2") (pintype "bidirectional"))
      (node (ref "J43") (pin "d22") (pinfunction "d22_d22") (pintype "bidirectional"))
      (node (ref "J43") (pin "d23") (pinfunction "d23_d23") (pintype "bidirectional"))
      (node (ref "J43") (pin "d24") (pinfunction "d24_d24") (pintype "bidirectional"))
      (node (ref "J43") (pin "d25") (pinfunction "d25_d25") (pintype "bidirectional"))
      (node (ref "J43") (pin "d26") (pinfunction "d26_d26") (pintype "bidirectional"))
      (node (ref "J43") (pin "d27") (pinfunction "d27_d27") (pintype "bidirectional"))
      (node (ref "J43") (pin "d28") (pinfunction "d28_d28") (pintype "bidirectional"))
      (node (ref "J43") (pin "d3") (pinfunction "d3_d3") (pintype "bidirectional"))
      (node (ref "J43") (pin "d31") (pinfunction "d31_d31") (pintype "bidirectional"))
      (node (ref "J43") (pin "d36") (pinfunction "d36_d36") (pintype "bidirectional"))
      (node (ref "J43") (pin "d4") (pinfunction "d4_d4") (pintype "bidirectional"))
      (node (ref "J43") (pin "d40") (pinfunction "d40_d40") (pintype "bidirectional"))
      (node (ref "J43") (pin "d5") (pinfunction "d5_d5") (pintype "bidirectional"))
      (node (ref "J43") (pin "d6") (pinfunction "d6_d6") (pintype "bidirectional"))
      (node (ref "J43") (pin "d7") (pinfunction "d7_d7") (pintype "bidirectional"))
      (node (ref "J43") (pin "e1") (pinfunction "e1_e1") (pintype "bidirectional"))
      (node (ref "J43") (pin "e10") (pinfunction "e10_e10") (pintype "bidirectional"))
      (node (ref "J43") (pin "e11") (pinfunction "e11_e11") (pintype "bidirectional"))
      (node (ref "J43") (pin "e12") (pinfunction "e12_e12") (pintype "bidirectional"))
      (node (ref "J43") (pin "e13") (pinfunction "e13_e13") (pintype "bidirectional"))
      (node (ref "J43") (pin "e14") (pinfunction "e14_e14") (pintype "bidirectional"))
      (node (ref "J43") (pin "e15") (pinfunction "e15_e15") (pintype "bidirectional"))
      (node (ref "J43") (pin "e16") (pinfunction "e16_e16") (pintype "bidirectional"))
      (node (ref "J43") (pin "e17") (pinfunction "e17_e17") (pintype "bidirectional"))
      (node (ref "J43") (pin "e18") (pinfunction "e18_e18") (pintype "bidirectional"))
      (node (ref "J43") (pin "e19") (pinfunction "e19_e19") (pintype "bidirectional"))
      (node (ref "J43") (pin "e2") (pinfunction "e2_e2") (pintype "bidirectional"))
      (node (ref "J43") (pin "e20") (pinfunction "e20_e20") (pintype "bidirectional"))
      (node (ref "J43") (pin "e21") (pinfunction "e21_e21") (pintype "bidirectional"))
      (node (ref "J43") (pin "e22") (pinfunction "e22_e22") (pintype "bidirectional"))
      (node (ref "J43") (pin "e23") (pinfunction "e23_e23") (pintype "bidirectional"))
      (node (ref "J43") (pin "e24") (pinfunction "e24_e24") (pintype "bidirectional"))
      (node (ref "J43") (pin "e25") (pinfunction "e25_e25") (pintype "bidirectional"))
      (node (ref "J43") (pin "e26") (pinfunction "e26_e26") (pintype "bidirectional"))
      (node (ref "J43") (pin "e27") (pinfunction "e27_e27") (pintype "bidirectional"))
      (node (ref "J43") (pin "e28") (pinfunction "e28_e28") (pintype "bidirectional"))
      (node (ref "J43") (pin "e29") (pinfunction "e29_e29") (pintype "bidirectional"))
      (node (ref "J43") (pin "e3") (pinfunction "e3_e3") (pintype "bidirectional"))
      (node (ref "J43") (pin "e30") (pinfunction "e30_e30") (pintype "bidirectional"))
      (node (ref "J43") (pin "e33") (pinfunction "e33_e33") (pintype "bidirectional"))
      (node (ref "J43") (pin "e36") (pinfunction "e36_e36") (pintype "bidirectional"))
      (node (ref "J43") (pin "e4") (pinfunction "e4_e4") (pintype "bidirectional"))
      (node (ref "J43") (pin "e40") (pinfunction "e40_e40") (pintype "bidirectional"))
      (node (ref "J43") (pin "e5") (pinfunction "e5_e5") (pintype "bidirectional"))
      (node (ref "J43") (pin "e6") (pinfunction "e6_e6") (pintype "bidirectional"))
      (node (ref "J43") (pin "e7") (pinfunction "e7_e7") (pintype "bidirectional"))
      (node (ref "J43") (pin "e8") (pinfunction "e8_e8") (pintype "bidirectional"))
      (node (ref "J43") (pin "e9") (pinfunction "e9_e9") (pintype "bidirectional"))
      (node (ref "J43") (pin "f1") (pinfunction "f1_f1") (pintype "bidirectional"))
      (node (ref "J43") (pin "f10") (pinfunction "f10_f10") (pintype "bidirectional"))
      (node (ref "J43") (pin "f11") (pinfunction "f11_f11") (pintype "bidirectional"))
      (node (ref "J43") (pin "f12") (pinfunction "f12_f12") (pintype "bidirectional"))
      (node (ref "J43") (pin "f13") (pinfunction "f13_f13") (pintype "bidirectional"))
      (node (ref "J43") (pin "f14") (pinfunction "f14_f14") (pintype "bidirectional"))
      (node (ref "J43") (pin "f15") (pinfunction "f15_f15") (pintype "bidirectional"))
      (node (ref "J43") (pin "f16") (pinfunction "f16_f16") (pintype "bidirectional"))
      (node (ref "J43") (pin "f17") (pinfunction "f17_f17") (pintype "bidirectional"))
      (node (ref "J43") (pin "f18") (pinfunction "f18_f18") (pintype "bidirectional"))
      (node (ref "J43") (pin "f19") (pinfunction "f19_f19") (pintype "bidirectional"))
      (node (ref "J43") (pin "f2") (pinfunction "f2_f2") (pintype "bidirectional"))
      (node (ref "J43") (pin "f20") (pinfunction "f20_f20") (pintype "bidirectional"))
      (node (ref "J43") (pin "f21") (pinfunction "f21_f21") (pintype "bidirectional"))
      (node (ref "J43") (pin "f22") (pinfunction "f22_f22") (pintype "bidirectional"))
      (node (ref "J43") (pin "f23") (pinfunction "f23_f23") (pintype "bidirectional"))
      (node (ref "J43") (pin "f24") (pinfunction "f24_f24") (pintype "bidirectional"))
      (node (ref "J43") (pin "f25") (pinfunction "f25_f25") (pintype "bidirectional"))
      (node (ref "J43") (pin "f26") (pinfunction "f26_f26") (pintype "bidirectional"))
      (node (ref "J43") (pin "f29") (pinfunction "f29_f29") (pintype "bidirectional"))
      (node (ref "J43") (pin "f3") (pinfunction "f3_f3") (pintype "bidirectional"))
      (node (ref "J43") (pin "f33") (pinfunction "f33_f33") (pintype "bidirectional"))
      (node (ref "J43") (pin "f36") (pinfunction "f36_f36") (pintype "bidirectional"))
      (node (ref "J43") (pin "f4") (pinfunction "f4_f4") (pintype "bidirectional"))
      (node (ref "J43") (pin "f40") (pinfunction "f40_f40") (pintype "bidirectional"))
      (node (ref "J43") (pin "f5") (pinfunction "f5_f5") (pintype "bidirectional"))
      (node (ref "J43") (pin "f6") (pinfunction "f6_f6") (pintype "bidirectional"))
      (node (ref "J43") (pin "f7") (pinfunction "f7_f7") (pintype "bidirectional"))
      (node (ref "J43") (pin "f8") (pinfunction "f8_f8") (pintype "bidirectional"))
      (node (ref "J43") (pin "f9") (pinfunction "f9_f9") (pintype "bidirectional"))
      (node (ref "J43") (pin "g1") (pinfunction "g1_g1") (pintype "bidirectional"))
      (node (ref "J43") (pin "g10") (pinfunction "g10_g10") (pintype "bidirectional"))
      (node (ref "J43") (pin "g13") (pinfunction "g13_g13") (pintype "bidirectional"))
      (node (ref "J43") (pin "g14") (pinfunction "g14_g14") (pintype "bidirectional"))
      (node (ref "J43") (pin "g15") (pinfunction "g15_g15") (pintype "bidirectional"))
      (node (ref "J43") (pin "g16") (pinfunction "g16_g16") (pintype "bidirectional"))
      (node (ref "J43") (pin "g17") (pinfunction "g17_g17") (pintype "bidirectional"))
      (node (ref "J43") (pin "g18") (pinfunction "g18_g18") (pintype "bidirectional"))
      (node (ref "J43") (pin "g19") (pinfunction "g19_g19") (pintype "bidirectional"))
      (node (ref "J43") (pin "g2") (pinfunction "g2_g2") (pintype "bidirectional"))
      (node (ref "J43") (pin "g20") (pinfunction "g20_g20") (pintype "bidirectional"))
      (node (ref "J43") (pin "g21") (pinfunction "g21_g21") (pintype "bidirectional"))
      (node (ref "J43") (pin "g22") (pinfunction "g22_g22") (pintype "bidirectional"))
      (node (ref "J43") (pin "g25") (pinfunction "g25_g25") (pintype "bidirectional"))
      (node (ref "J43") (pin "g26") (pinfunction "g26_g26") (pintype "bidirectional"))
      (node (ref "J43") (pin "g27") (pinfunction "g27_g27") (pintype "bidirectional"))
      (node (ref "J43") (pin "g3") (pinfunction "g3_g3") (pintype "bidirectional"))
      (node (ref "J43") (pin "g30") (pinfunction "g30_g30") (pintype "bidirectional"))
      (node (ref "J43") (pin "g33") (pinfunction "g33_g33") (pintype "bidirectional"))
      (node (ref "J43") (pin "g36") (pinfunction "g36_g36") (pintype "bidirectional"))
      (node (ref "J43") (pin "g4") (pinfunction "g4_g4") (pintype "bidirectional"))
      (node (ref "J43") (pin "g40") (pinfunction "g40_g40") (pintype "bidirectional"))
      (node (ref "J43") (pin "g5") (pinfunction "g5_g5") (pintype "bidirectional"))
      (node (ref "J43") (pin "g6") (pinfunction "g6_g6") (pintype "bidirectional"))
      (node (ref "J43") (pin "g7") (pinfunction "g7_g7") (pintype "bidirectional"))
      (node (ref "J43") (pin "g8") (pinfunction "g8_g8") (pintype "bidirectional"))
      (node (ref "J43") (pin "g9") (pinfunction "g9_g9") (pintype "bidirectional"))
      (node (ref "J43") (pin "h1") (pinfunction "h1_h1") (pintype "bidirectional"))
      (node (ref "J43") (pin "h10") (pinfunction "h10_h10") (pintype "bidirectional"))
      (node (ref "J43") (pin "h11") (pinfunction "h11_h11") (pintype "bidirectional"))
      (node (ref "J43") (pin "h12") (pinfunction "h12_h12") (pintype "bidirectional"))
      (node (ref "J43") (pin "h13") (pinfunction "h13_h13") (pintype "bidirectional"))
      (node (ref "J43") (pin "h14") (pinfunction "h14_h14") (pintype "bidirectional"))
      (node (ref "J43") (pin "h15") (pinfunction "h15_h15") (pintype "bidirectional"))
      (node (ref "J43") (pin "h16") (pinfunction "h16_h16") (pintype "bidirectional"))
      (node (ref "J43") (pin "h19") (pinfunction "h19_h19") (pintype "bidirectional"))
      (node (ref "J43") (pin "h2") (pinfunction "h2_h2") (pintype "bidirectional"))
      (node (ref "J43") (pin "h20") (pinfunction "h20_h20") (pintype "bidirectional"))
      (node (ref "J43") (pin "h21") (pinfunction "h21_h21") (pintype "bidirectional"))
      (node (ref "J43") (pin "h22") (pinfunction "h22_h22") (pintype "bidirectional"))
      (node (ref "J43") (pin "h23") (pinfunction "h23_h23") (pintype "bidirectional"))
      (node (ref "J43") (pin "h24") (pinfunction "h24_h24") (pintype "bidirectional"))
      (node (ref "J43") (pin "h25") (pinfunction "h25_h25") (pintype "bidirectional"))
      (node (ref "J43") (pin "h26") (pinfunction "h26_h26") (pintype "bidirectional"))
      (node (ref "J43") (pin "h27") (pinfunction "h27_h27") (pintype "bidirectional"))
      (node (ref "J43") (pin "h28") (pinfunction "h28_h28") (pintype "bidirectional"))
      (node (ref "J43") (pin "h3") (pinfunction "h3_h3") (pintype "bidirectional"))
      (node (ref "J43") (pin "h33") (pinfunction "h33_h33") (pintype "bidirectional"))
      (node (ref "J43") (pin "h36") (pinfunction "h36_h36") (pintype "bidirectional"))
      (node (ref "J43") (pin "h4") (pinfunction "h4_h4") (pintype "bidirectional"))
      (node (ref "J43") (pin "h40") (pinfunction "h40_h40") (pintype "bidirectional"))
      (node (ref "J43") (pin "h7") (pinfunction "h7_h7") (pintype "bidirectional"))
      (node (ref "J43") (pin "h8") (pinfunction "h8_h8") (pintype "bidirectional"))
      (node (ref "J43") (pin "h9") (pinfunction "h9_h9") (pintype "bidirectional"))
      (node (ref "J43") (pin "j1") (pinfunction "j1_j1") (pintype "bidirectional"))
      (node (ref "J43") (pin "j10") (pinfunction "j10_j10") (pintype "bidirectional"))
      (node (ref "J43") (pin "j11") (pinfunction "j11_j11") (pintype "bidirectional"))
      (node (ref "J43") (pin "j12") (pinfunction "j12_j12") (pintype "bidirectional"))
      (node (ref "J43") (pin "j13") (pinfunction "j13_j13") (pintype "bidirectional"))
      (node (ref "J43") (pin "j14") (pinfunction "j14_j14") (pintype "bidirectional"))
      (node (ref "J43") (pin "j15") (pinfunction "j15_j15") (pintype "bidirectional"))
      (node (ref "J43") (pin "j16") (pinfunction "j16_j16") (pintype "bidirectional"))
      (node (ref "J43") (pin "j17") (pinfunction "j17_j17") (pintype "bidirectional"))
      (node (ref "J43") (pin "j18") (pinfunction "j18_j18") (pintype "bidirectional"))
      (node (ref "J43") (pin "j19") (pinfunction "j19_j19") (pintype "bidirectional"))
      (node (ref "J43") (pin "j2") (pinfunction "j2_j2") (pintype "bidirectional"))
      (node (ref "J43") (pin "j20") (pinfunction "j20_j20") (pintype "bidirectional"))
      (node (ref "J43") (pin "j21") (pinfunction "j21_j21") (pintype "bidirectional"))
      (node (ref "J43") (pin "j22") (pinfunction "j22_j22") (pintype "bidirectional"))
      (node (ref "J43") (pin "j23") (pinfunction "j23_j23") (pintype "bidirectional"))
      (node (ref "J43") (pin "j24") (pinfunction "j24_j24") (pintype "bidirectional"))
      (node (ref "J43") (pin "j25") (pinfunction "j25_j25") (pintype "bidirectional"))
      (node (ref "J43") (pin "j26") (pinfunction "j26_j26") (pintype "bidirectional"))
      (node (ref "J43") (pin "j27") (pinfunction "j27_j27") (pintype "bidirectional"))
      (node (ref "J43") (pin "j28") (pinfunction "j28_j28") (pintype "bidirectional"))
      (node (ref "J43") (pin "j29") (pinfunction "j29_j29") (pintype "bidirectional"))
      (node (ref "J43") (pin "j3") (pinfunction "j3_j3") (pintype "bidirectional"))
      (node (ref "J43") (pin "j30") (pinfunction "j30_j30") (pintype "bidirectional"))
      (node (ref "J43") (pin "j33") (pinfunction "j33_j33") (pintype "bidirectional"))
      (node (ref "J43") (pin "j36") (pinfunction "j36_j36") (pintype "bidirectional"))
      (node (ref "J43") (pin "j4") (pinfunction "j4_j4") (pintype "bidirectional"))
      (node (ref "J43") (pin "j40") (pinfunction "j40_j40") (pintype "bidirectional"))
      (node (ref "J43") (pin "j5") (pinfunction "j5_j5") (pintype "bidirectional"))
      (node (ref "J43") (pin "j6") (pinfunction "j6_j6") (pintype "bidirectional"))
      (node (ref "J43") (pin "j7") (pinfunction "j7_j7") (pintype "bidirectional"))
      (node (ref "J43") (pin "j8") (pinfunction "j8_j8") (pintype "bidirectional"))
      (node (ref "J43") (pin "j9") (pinfunction "j9_j9") (pintype "bidirectional"))
      (node (ref "J43") (pin "k1") (pinfunction "k1_k1") (pintype "bidirectional"))
      (node (ref "J43") (pin "k10") (pinfunction "k10_k10") (pintype "bidirectional"))
      (node (ref "J43") (pin "k11") (pinfunction "k11_k11") (pintype "bidirectional"))
      (node (ref "J43") (pin "k12") (pinfunction "k12_k12") (pintype "bidirectional"))
      (node (ref "J43") (pin "k13") (pinfunction "k13_k13") (pintype "bidirectional"))
      (node (ref "J43") (pin "k14") (pinfunction "k14_k14") (pintype "bidirectional"))
      (node (ref "J43") (pin "k15") (pinfunction "k15_k15") (pintype "bidirectional"))
      (node (ref "J43") (pin "k16") (pinfunction "k16_k16") (pintype "bidirectional"))
      (node (ref "J43") (pin "k17") (pinfunction "k17_k17") (pintype "bidirectional"))
      (node (ref "J43") (pin "k18") (pinfunction "k18_k18") (pintype "bidirectional"))
      (node (ref "J43") (pin "k19") (pinfunction "k19_k19") (pintype "bidirectional"))
      (node (ref "J43") (pin "k2") (pinfunction "k2_k2") (pintype "bidirectional"))
      (node (ref "J43") (pin "k20") (pinfunction "k20_k20") (pintype "bidirectional"))
      (node (ref "J43") (pin "k21") (pinfunction "k21_k21") (pintype "bidirectional"))
      (node (ref "J43") (pin "k22") (pinfunction "k22_k22") (pintype "bidirectional"))
      (node (ref "J43") (pin "k23") (pinfunction "k23_k23") (pintype "bidirectional"))
      (node (ref "J43") (pin "k24") (pinfunction "k24_k24") (pintype "bidirectional"))
      (node (ref "J43") (pin "k25") (pinfunction "k25_k25") (pintype "bidirectional"))
      (node (ref "J43") (pin "k26") (pinfunction "k26_k26") (pintype "bidirectional"))
      (node (ref "J43") (pin "k27") (pinfunction "k27_k27") (pintype "bidirectional"))
      (node (ref "J43") (pin "k3") (pinfunction "k3_k3") (pintype "bidirectional"))
      (node (ref "J43") (pin "k30") (pinfunction "k30_k30") (pintype "bidirectional"))
      (node (ref "J43") (pin "k31") (pinfunction "k31_k31") (pintype "bidirectional"))
      (node (ref "J43") (pin "k32") (pinfunction "k32_k32") (pintype "bidirectional"))
      (node (ref "J43") (pin "k33") (pinfunction "k33_k33") (pintype "bidirectional"))
      (node (ref "J43") (pin "k36") (pinfunction "k36_k36") (pintype "bidirectional"))
      (node (ref "J43") (pin "k4") (pinfunction "k4_k4") (pintype "bidirectional"))
      (node (ref "J43") (pin "k40") (pinfunction "k40_k40") (pintype "bidirectional"))
      (node (ref "J43") (pin "k5") (pinfunction "k5_k5") (pintype "bidirectional"))
      (node (ref "J43") (pin "k6") (pinfunction "k6_k6") (pintype "bidirectional"))
      (node (ref "J43") (pin "k7") (pinfunction "k7_k7") (pintype "bidirectional"))
      (node (ref "J43") (pin "k8") (pinfunction "k8_k8") (pintype "bidirectional"))
      (node (ref "J43") (pin "k9") (pinfunction "k9_k9") (pintype "bidirectional"))
      (node (ref "J44") (pin "2") (pinfunction "2_2") (pintype "bidirectional"))
      (node (ref "J45") (pin "2") (pinfunction "2_2") (pintype "bidirectional"))
      (node (ref "J46") (pin "2") (pinfunction "2_2") (pintype "bidirectional"))
      (node (ref "J47") (pin "2") (pinfunction "2_2") (pintype "bidirectional"))
      (node (ref "J48") (pin "2") (pinfunction "2_2") (pintype "bidirectional"))
      (node (ref "J49") (pin "2") (pinfunction "2_2") (pintype "bidirectional"))
      (node (ref "J50") (pin "2") (pinfunction "2_2") (pintype "bidirectional"))
      (node (ref "J51") (pin "1") (pinfunction "1_1") (pintype "bidirectional"))
      (node (ref "J51") (pin "10") (pinfunction "10_10") (pintype "bidirectional"))
      (node (ref "J51") (pin "13") (pinfunction "13_13") (pintype "bidirectional"))
      (node (ref "J51") (pin "16") (pinfunction "16_16") (pintype "bidirectional"))
      (node (ref "J51") (pin "19") (pinfunction "19_19") (pintype "bidirectional"))
      (node (ref "J51") (pin "22") (pinfunction "22_22") (pintype "bidirectional"))
      (node (ref "J51") (pin "25") (pinfunction "25_25") (pintype "bidirectional"))
      (node (ref "J51") (pin "4") (pinfunction "4_4") (pintype "bidirectional"))
      (node (ref "J51") (pin "7") (pinfunction "7_7") (pintype "bidirectional"))
      (node (ref "TR23") (pin "1") (pinfunction "P1_1") (pintype "passive"))
      (node (ref "TR23") (pin "2") (pinfunction "P1_2") (pintype "passive"))
      (node (ref "TR23") (pin "5") (pinfunction "NC_5") (pintype "passive"))
      (node (ref "TR24") (pin "1") (pinfunction "P1_1") (pintype "passive"))
      (node (ref "TR24") (pin "2") (pinfunction "P1_2") (pintype "passive"))
      (node (ref "TR24") (pin "5") (pinfunction "NC_5") (pintype "passive"))
      (node (ref "TR25") (pin "1") (pinfunction "P1_1") (pintype "passive"))
      (node (ref "TR25") (pin "2") (pinfunction "P1_2") (pintype "passive"))
      (node (ref "TR25") (pin "5") (pinfunction "NC_5") (pintype "passive"))
      (node (ref "TR26") (pin "1") (pinfunction "P1_1") (pintype "passive"))
      (node (ref "TR26") (pin "2") (pinfunction "P1_2") (pintype "passive"))
      (node (ref "TR26") (pin "5") (pinfunction "NC_5") (pintype "passive"))
      (node (ref "TR27") (pin "1") (pinfunction "P1_1") (pintype "passive"))
      (node (ref "TR27") (pin "2") (pinfunction "P1_2") (pintype "passive"))
      (node (ref "TR27") (pin "5") (pinfunction "NC_5") (pintype "passive"))
      (node (ref "TR28") (pin "1") (pinfunction "P1_1") (pintype "passive"))
      (node (ref "TR28") (pin "2") (pinfunction "P1_2") (pintype "passive"))
      (node (ref "TR28") (pin "5") (pinfunction "NC_5") (pintype "passive"))
      (node (ref "TR29") (pin "1") (pinfunction "P1_1") (pintype "passive"))
      (node (ref "TR29") (pin "2") (pinfunction "P1_2") (pintype "passive"))
      (node (ref "TR29") (pin "5") (pinfunction "NC_5") (pintype "passive"))
      (node (ref "TR30") (pin "1") (pinfunction "P1_1") (pintype "passive"))
      (node (ref "TR30") (pin "2") (pinfunction "P1_2") (pintype "passive"))
      (node (ref "TR30") (pin "5") (pinfunction "NC_5") (pintype "passive"))
    )
    (net (code "83") (name "N6V0A") (class "Default")
      (node (ref "J43") (pin "f27") (pinfunction "f27_f27") (pintype "bidirectional"))
      (node (ref "J43") (pin "f28") (pinfunction "f28_f28") (pintype "bidirectional"))
    )
    (net (code "84") (name "N12V0A") (class "Default")
      (node (ref "J43") (pin "d32") (pinfunction "d32_d32") (pintype "bidirectional"))
      (node (ref "J43") (pin "d33") (pinfunction "d33_d33") (pintype "bidirectional"))
    )
    (net (code "85") (name "Net-(J42-Pad1)") (class "Default")
      (node (ref "J42") (pin "1") (pinfunction "1_1") (pintype "bidirectional"))
      (node (ref "TR23") (pin "3") (pinfunction "P1_3") (pintype "passive"))
    )
    (net (code "86") (name "Net-(J44-Pad1)") (class "Default")
      (node (ref "J44") (pin "1") (pinfunction "1_1") (pintype "bidirectional"))
      (node (ref "TR24") (pin "3") (pinfunction "P1_3") (pintype "passive"))
    )
    (net (code "87") (name "Net-(J45-Pad1)") (class "Default")
      (node (ref "J45") (pin "1") (pinfunction "1_1") (pintype "bidirectional"))
      (node (ref "TR25") (pin "3") (pinfunction "P1_3") (pintype "passive"))
    )
    (net (code "88") (name "Net-(J46-Pad1)") (class "Default")
      (node (ref "J46") (pin "1") (pinfunction "1_1") (pintype "bidirectional"))
      (node (ref "TR26") (pin "3") (pinfunction "P1_3") (pintype "passive"))
    )
    (net (code "89") (name "Net-(J47-Pad1)") (class "Default")
      (node (ref "J47") (pin "1") (pinfunction "1_1") (pintype "bidirectional"))
      (node (ref "TR27") (pin "3") (pinfunction "P1_3") (pintype "passive"))
    )
    (net (code "90") (name "Net-(J48-Pad1)") (class "Default")
      (node (ref "J48") (pin "1") (pinfunction "1_1") (pintype "bidirectional"))
      (node (ref "TR28") (pin "3") (pinfunction "P1_3") (pintype "passive"))
    )
    (net (code "91") (name "Net-(J49-Pad1)") (class "Default")
      (node (ref "J49") (pin "1") (pinfunction "1_1") (pintype "bidirectional"))
      (node (ref "TR29") (pin "3") (pinfunction "P1_3") (pintype "passive"))
    )
    (net (code "92") (name "Net-(J50-Pad1)") (class "Default")
      (node (ref "J50") (pin "1") (pinfunction "1_1") (pintype "bidirectional"))
      (node (ref "TR30") (pin "3") (pinfunction "P1_3") (pintype "passive"))
    )
    (net (code "93") (name "P3V3") (class "Default")
      (node (ref "J43") (pin "c30") (pinfunction "c30_c30") (pintype "bidirectional"))
      (node (ref "J43") (pin "c31") (pinfunction "c31_c31") (pintype "bidirectional"))
    )
    (net (code "94") (name "P3V3_MP") (class "Default")
      (node (ref "J43") (pin "c33") (pinfunction "c33_c33") (pintype "bidirectional"))
      (node (ref "J51") (pin "30") (pinfunction "30_30") (pintype "bidirectional"))
    )
    (net (code "95") (name "P6V0A") (class "Default")
      (node (ref "J43") (pin "a28") (pinfunction "a28_a28") (pintype "bidirectional"))
      (node (ref "J43") (pin "a29") (pinfunction "a29_a29") (pintype "bidirectional"))
      (node (ref "J43") (pin "b28") (pinfunction "b28_b28") (pintype "bidirectional"))
      (node (ref "J43") (pin "b29") (pinfunction "b29_b29") (pintype "bidirectional"))
    )
    (net (code "96") (name "P12V0A") (class "Default")
      (node (ref "J43") (pin "d29") (pinfunction "d29_d29") (pintype "bidirectional"))
      (node (ref "J43") (pin "d30") (pinfunction "d30_d30") (pintype "bidirectional"))
      (node (ref "J51") (pin "28") (pinfunction "28_28") (pintype "bidirectional"))
      (node (ref "J51") (pin "29") (pinfunction "29_29") (pintype "bidirectional"))
    )
    (net (code "97") (name "unconnected-(J43-Padb31)") (class "Default")
      (node (ref "J43") (pin "b31") (pinfunction "b31_b31") (pintype "bidirectional"))
    )
    (net (code "98") (name "unconnected-(J43-Padb32)") (class "Default")
      (node (ref "J43") (pin "b32") (pinfunction "b32_b32") (pintype "bidirectional"))
    )
    (net (code "99") (name "unconnected-(J43-Pade31)") (class "Default")
      (node (ref "J43") (pin "e31") (pinfunction "e31_e31") (pintype "bidirectional"))
    )
    (net (code "100") (name "unconnected-(J43-Pade32)") (class "Default")
      (node (ref "J43") (pin "e32") (pinfunction "e32_e32") (pintype "bidirectional"))
    )
    (net (code "101") (name "unconnected-(J43-Padg28)") (class "Default")
      (node (ref "J43") (pin "g28") (pinfunction "g28_g28") (pintype "bidirectional"))
    )
    (net (code "102") (name "unconnected-(J43-Padh29)") (class "Default")
      (node (ref "J43") (pin "h29") (pinfunction "h29_h29") (pintype "bidirectional"))
    )
    (net (code "103") (name "unconnected-(J43-Padh30)") (class "Default")
      (node (ref "J43") (pin "h30") (pinfunction "h30_h30") (pintype "bidirectional"))
    )
    (net (code "104") (name "unconnected-(J43-Padk28)") (class "Default")
      (node (ref "J43") (pin "k28") (pinfunction "k28_k28") (pintype "bidirectional"))
    )
    (net (code "105") (name "unconnected-(J43-Padk29)") (class "Default")
      (node (ref "J43") (pin "k29") (pinfunction "k29_k29") (pintype "bidirectional"))
    )
  )
)
